# BalEv_FPTG_IO_v1_0.net
KiCad netlist of a schematic drawn in Altium Designer
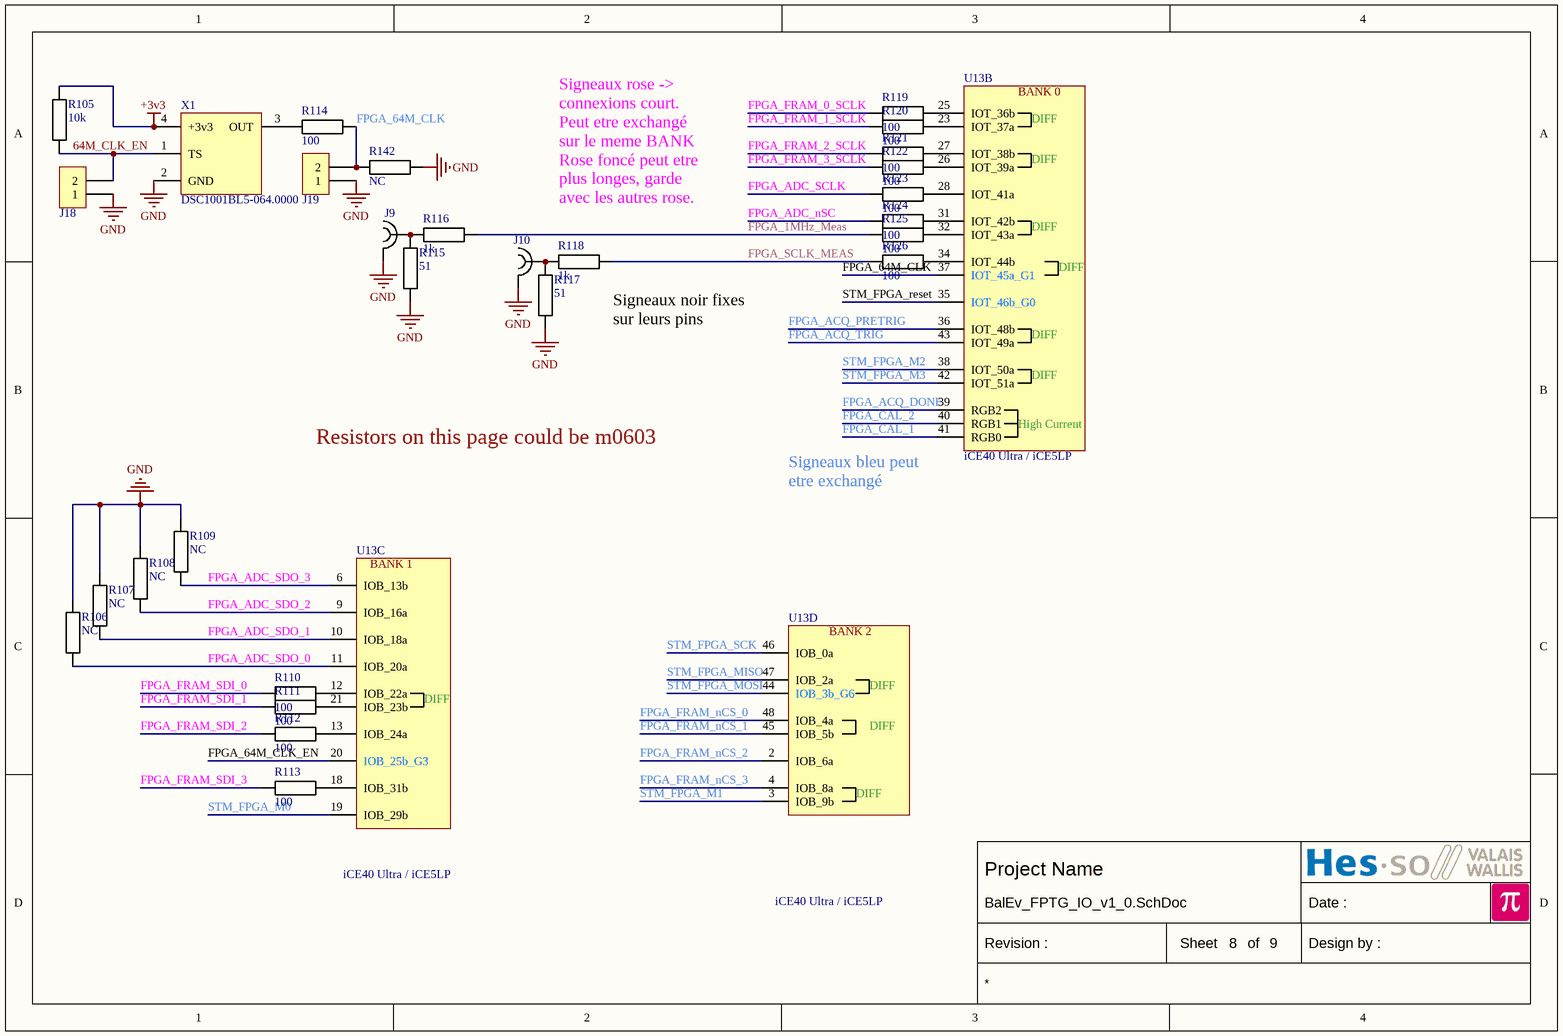
[diagram p0: BalEv_FPTG_IO_v1_0.SchDoc]

(export (version "E")
  (design (tool "Eeschema 10.0.6"))
  (components
    (comp (ref "J9")
      (value "CONSMA001-SMD-G")
      (footprint "SMA SMD Vertical Linx CONSMA001-SMD-G")
      (description "SMA TH VERTICAL LINX CONSMA001-SMD-G")
      (libsource (lib "Connector") (part "SMA SMD VERTICAL LINX CONSMA001-SMD-G"))
    )
    (comp (ref "J10")
      (value "CONSMA001-SMD-G")
      (footprint "SMA SMD Vertical Linx CONSMA001-SMD-G")
      (description "SMA TH VERTICAL LINX CONSMA001-SMD-G")
      (libsource (lib "Connector") (part "SMA SMD VERTICAL LINX CONSMA001-SMD-G"))
    )
    (comp (ref "J18")
      (value "*")
      (footprint "PinHeader1x2 P2.54")
      (description "Plug connector")
      (libsource (lib "PinHeader") (part "PinHeader1x2"))
    )
    (comp (ref "J19")
      (value "*")
      (footprint "PinHeader1x2 P1.27")
      (description "Plug connector")
      (libsource (lib "PinHeader") (part "PinHeader1x2"))
    )
    (comp (ref "R105")
      (value "10k")
      (footprint "RESISTOR 1005 REFLOW")
      (description "Resistor")
      (libsource (lib "Resistor") (part "Resistor"))
    )
    (comp (ref "R106")
      (value "NC")
      (footprint "RESISTOR 1005 REFLOW")
      (description "Resistor")
      (libsource (lib "Resistor") (part "Resistor"))
    )
    (comp (ref "R107")
      (value "NC")
      (footprint "RESISTOR 1005 REFLOW")
      (description "Resistor")
      (libsource (lib "Resistor") (part "Resistor"))
    )
    (comp (ref "R108")
      (value "NC")
      (footprint "RESISTOR 1005 REFLOW")
      (description "Resistor")
      (libsource (lib "Resistor") (part "Resistor"))
    )
    (comp (ref "R109")
      (value "NC")
      (footprint "RESISTOR 1005 REFLOW")
      (description "Resistor")
      (libsource (lib "Resistor") (part "Resistor"))
    )
    (comp (ref "R110")
      (value "100")
      (footprint "RESISTOR 1005 REFLOW")
      (description "Resistor")
      (libsource (lib "Resistor") (part "Resistor"))
    )
    (comp (ref "R111")
      (value "100")
      (footprint "RESISTOR 1005 REFLOW")
      (description "Resistor")
      (libsource (lib "Resistor") (part "Resistor"))
    )
    (comp (ref "R112")
      (value "100")
      (footprint "RESISTOR 1005 REFLOW")
      (description "Resistor")
      (libsource (lib "Resistor") (part "Resistor"))
    )
    (comp (ref "R113")
      (value "100")
      (footprint "RESISTOR 1005 REFLOW")
      (description "Resistor")
      (libsource (lib "Resistor") (part "Resistor"))
    )
    (comp (ref "R114")
      (value "100")
      (footprint "RESISTOR 1005 REFLOW")
      (description "Resistor")
      (libsource (lib "Resistor") (part "Resistor"))
    )
    (comp (ref "R115")
      (value "51")
      (footprint "RESISTOR 1005 REFLOW")
      (description "Resistor")
      (libsource (lib "Resistor") (part "Resistor"))
    )
    (comp (ref "R116")
      (value "1k")
      (footprint "RESISTOR 1005 REFLOW")
      (description "Resistor")
      (libsource (lib "Resistor") (part "Resistor"))
    )
    (comp (ref "R117")
      (value "51")
      (footprint "RESISTOR 1005 REFLOW")
      (description "Resistor")
      (libsource (lib "Resistor") (part "Resistor"))
    )
    (comp (ref "R118")
      (value "1k")
      (footprint "RESISTOR 1005 REFLOW")
      (description "Resistor")
      (libsource (lib "Resistor") (part "Resistor"))
    )
    (comp (ref "R119")
      (value "100")
      (footprint "RESISTOR 1005 REFLOW")
      (description "Resistor")
      (libsource (lib "Resistor") (part "Resistor"))
    )
    (comp (ref "R120")
      (value "100")
      (footprint "RESISTOR 1005 REFLOW")
      (description "Resistor")
      (libsource (lib "Resistor") (part "Resistor"))
    )
    (comp (ref "R121")
      (value "100")
      (footprint "RESISTOR 1005 REFLOW")
      (description "Resistor")
      (libsource (lib "Resistor") (part "Resistor"))
    )
    (comp (ref "R122")
      (value "100")
      (footprint "RESISTOR 1005 REFLOW")
      (description "Resistor")
      (libsource (lib "Resistor") (part "Resistor"))
    )
    (comp (ref "R123")
      (value "100")
      (footprint "RESISTOR 1005 REFLOW")
      (description "Resistor")
      (libsource (lib "Resistor") (part "Resistor"))
    )
    (comp (ref "R124")
      (value "100")
      (footprint "RESISTOR 1005 REFLOW")
      (description "Resistor")
      (libsource (lib "Resistor") (part "Resistor"))
    )
    (comp (ref "R125")
      (value "100")
      (footprint "RESISTOR 1005 REFLOW")
      (description "Resistor")
      (libsource (lib "Resistor") (part "Resistor"))
    )
    (comp (ref "R126")
      (value "100")
      (footprint "RESISTOR 1005 REFLOW")
      (description "Resistor")
      (libsource (lib "Resistor") (part "Resistor"))
    )
    (comp (ref "R142")
      (value "NC")
      (footprint "RESISTOR 1005 REFLOW")
      (description "Resistor")
      (libsource (lib "Resistor") (part "Resistor"))
    )
    (comp (ref "U13")
      (value "iCE40 Ultra / iCE5LP")
      (footprint "QFN50P700X700X100_HS-49N")
      (libsource (lib "IntegratedCircuit") (part "ICE5LP1K-SG48"))
    )
    (comp (ref "X1")
      (value "DSC1001BL5-064.0000")
      (footprint "Oscillator C5.0x3.2 Abracon ASFL1")
      (description "Oscillator C5.0x3.2 Abracon ASFL1")
      (libsource (lib "Oscillator") (part "Oscillator C5.0x3.2 Abracon ASFL1"))
    )
  )
  (nets
    (net (code "1") (name "+3v3") (class "Default")
      (node (ref "R105") (pin "2") (pinfunction "2_2") (pintype "passive"))
      (node (ref "X1") (pin "4") (pinfunction "+3v3_4") (pintype "passive"))
    )
    (net (code "2") (name "/64M_CLK_EN") (class "Default")
      (node (ref "J18") (pin "2") (pinfunction "2_2") (pintype "passive"))
      (node (ref "R105") (pin "1") (pinfunction "1_1") (pintype "passive"))
      (node (ref "X1") (pin "1") (pinfunction "TS_1") (pintype "passive"))
    )
    (net (code "3") (name "/FPGA_1MHz_Meas") (class "Default")
      (node (ref "R116") (pin "1") (pinfunction "1_1") (pintype "passive"))
      (node (ref "R125") (pin "2") (pinfunction "2_2") (pintype "passive"))
    )
    (net (code "4") (name "/FPGA_64M_CLK") (class "Default")
      (node (ref "J19") (pin "2") (pinfunction "2_2") (pintype "passive"))
      (node (ref "R114") (pin "1") (pinfunction "1_1") (pintype "passive"))
      (node (ref "R142") (pin "2") (pinfunction "2_2") (pintype "passive"))
      (node (ref "U13") (pin "37") (pinfunction "IOT_45a_G1_37") (pintype "passive"))
    )
    (net (code "5") (name "/FPGA_64M_CLK_EN") (class "Default")
      (node (ref "U13") (pin "20") (pinfunction "IOB_25b_G3_20") (pintype "passive"))
    )
    (net (code "6") (name "/FPGA_ACQ_DONE") (class "Default")
      (node (ref "U13") (pin "39") (pinfunction "RGB2_39") (pintype "passive"))
    )
    (net (code "7") (name "/FPGA_ACQ_PRETRIG") (class "Default")
      (node (ref "U13") (pin "36") (pinfunction "IOT_48b_36") (pintype "passive"))
    )
    (net (code "8") (name "/FPGA_ACQ_TRIG") (class "Default")
      (node (ref "U13") (pin "43") (pinfunction "IOT_49a_43") (pintype "passive"))
    )
    (net (code "9") (name "/FPGA_ADC_SCLK") (class "Default")
      (node (ref "R123") (pin "2") (pinfunction "2_2") (pintype "passive"))
    )
    (net (code "10") (name "/FPGA_ADC_SDO_0") (class "Default")
      (node (ref "R106") (pin "2") (pinfunction "2_2") (pintype "passive"))
      (node (ref "U13") (pin "11") (pinfunction "IOB_20a_11") (pintype "passive"))
    )
    (net (code "11") (name "/FPGA_ADC_SDO_1") (class "Default")
      (node (ref "R107") (pin "2") (pinfunction "2_2") (pintype "passive"))
      (node (ref "U13") (pin "10") (pinfunction "IOB_18a_10") (pintype "passive"))
    )
    (net (code "12") (name "/FPGA_ADC_SDO_2") (class "Default")
      (node (ref "R108") (pin "2") (pinfunction "2_2") (pintype "passive"))
      (node (ref "U13") (pin "9") (pinfunction "IOB_16a_9") (pintype "passive"))
    )
    (net (code "13") (name "/FPGA_ADC_SDO_3") (class "Default")
      (node (ref "R109") (pin "2") (pinfunction "2_2") (pintype "passive"))
      (node (ref "U13") (pin "6") (pinfunction "IOB_13b_6") (pintype "passive"))
    )
    (net (code "14") (name "/FPGA_ADC_nSC") (class "Default")
      (node (ref "R124") (pin "2") (pinfunction "2_2") (pintype "passive"))
    )
    (net (code "15") (name "/FPGA_CAL_1") (class "Default")
      (node (ref "U13") (pin "41") (pinfunction "RGB0_41") (pintype "passive"))
    )
    (net (code "16") (name "/FPGA_CAL_2") (class "Default")
      (node (ref "U13") (pin "40") (pinfunction "RGB1_40") (pintype "passive"))
    )
    (net (code "17") (name "/FPGA_FRAM_0_SCLK") (class "Default")
      (node (ref "R119") (pin "2") (pinfunction "2_2") (pintype "passive"))
    )
    (net (code "18") (name "/FPGA_FRAM_1_SCLK") (class "Default")
      (node (ref "R120") (pin "2") (pinfunction "2_2") (pintype "passive"))
    )
    (net (code "19") (name "/FPGA_FRAM_2_SCLK") (class "Default")
      (node (ref "R121") (pin "2") (pinfunction "2_2") (pintype "passive"))
    )
    (net (code "20") (name "/FPGA_FRAM_3_SCLK") (class "Default")
      (node (ref "R122") (pin "2") (pinfunction "2_2") (pintype "passive"))
    )
    (net (code "21") (name "/FPGA_FRAM_SDI_0") (class "Default")
      (node (ref "R110") (pin "2") (pinfunction "2_2") (pintype "passive"))
    )
    (net (code "22") (name "/FPGA_FRAM_SDI_1") (class "Default")
      (node (ref "R111") (pin "2") (pinfunction "2_2") (pintype "passive"))
    )
    (net (code "23") (name "/FPGA_FRAM_SDI_2") (class "Default")
      (node (ref "R112") (pin "2") (pinfunction "2_2") (pintype "passive"))
    )
    (net (code "24") (name "/FPGA_FRAM_SDI_3") (class "Default")
      (node (ref "R113") (pin "2") (pinfunction "2_2") (pintype "passive"))
    )
    (net (code "25") (name "/FPGA_FRAM_nCS_0") (class "Default")
      (node (ref "U13") (pin "48") (pinfunction "IOB_4a_48") (pintype "passive"))
    )
    (net (code "26") (name "/FPGA_FRAM_nCS_1") (class "Default")
      (node (ref "U13") (pin "45") (pinfunction "IOB_5b_45") (pintype "passive"))
    )
    (net (code "27") (name "/FPGA_FRAM_nCS_2") (class "Default")
      (node (ref "U13") (pin "2") (pinfunction "IOB_6a_2") (pintype "passive"))
    )
    (net (code "28") (name "/FPGA_FRAM_nCS_3") (class "Default")
      (node (ref "U13") (pin "4") (pinfunction "IOB_8a_4") (pintype "passive"))
    )
    (net (code "29") (name "/FPGA_SCLK_MEAS") (class "Default")
      (node (ref "R118") (pin "1") (pinfunction "1_1") (pintype "passive"))
      (node (ref "R126") (pin "2") (pinfunction "2_2") (pintype "passive"))
    )
    (net (code "30") (name "/STM_FPGA_M0") (class "Default")
      (node (ref "U13") (pin "19") (pinfunction "IOB_29b_19") (pintype "passive"))
    )
    (net (code "31") (name "/STM_FPGA_M1") (class "Default")
      (node (ref "U13") (pin "3") (pinfunction "IOB_9b_3") (pintype "passive"))
    )
    (net (code "32") (name "/STM_FPGA_M2") (class "Default")
      (node (ref "U13") (pin "38") (pinfunction "IOT_50a_38") (pintype "passive"))
    )
    (net (code "33") (name "/STM_FPGA_M3") (class "Default")
      (node (ref "U13") (pin "42") (pinfunction "IOT_51a_42") (pintype "passive"))
    )
    (net (code "34") (name "/STM_FPGA_MISO") (class "Default")
      (node (ref "U13") (pin "47") (pinfunction "IOB_2a_47") (pintype "passive"))
    )
    (net (code "35") (name "/STM_FPGA_MOSI") (class "Default")
      (node (ref "U13") (pin "44") (pinfunction "IOB_3b_G6_44") (pintype "passive"))
    )
    (net (code "36") (name "/STM_FPGA_SCK") (class "Default")
      (node (ref "U13") (pin "46") (pinfunction "IOB_0a_46") (pintype "passive"))
    )
    (net (code "37") (name "/STM_FPGA_reset") (class "Default")
      (node (ref "U13") (pin "35") (pinfunction "IOT_46b_G0_35") (pintype "passive"))
    )
    (net (code "38") (name "GND") (class "Default")
      (node (ref "J10") (pin "2") (pinfunction "2_2") (pintype "passive"))
      (node (ref "J18") (pin "1") (pinfunction "1_1") (pintype "passive"))
      (node (ref "J19") (pin "1") (pinfunction "1_1") (pintype "passive"))
      (node (ref "J9") (pin "2") (pinfunction "2_2") (pintype "passive"))
      (node (ref "R106") (pin "1") (pinfunction "1_1") (pintype "passive"))
      (node (ref "R107") (pin "1") (pinfunction "1_1") (pintype "passive"))
      (node (ref "R108") (pin "1") (pinfunction "1_1") (pintype "passive"))
      (node (ref "R109") (pin "1") (pinfunction "1_1") (pintype "passive"))
      (node (ref "R115") (pin "2") (pinfunction "2_2") (pintype "passive"))
      (node (ref "R117") (pin "2") (pinfunction "2_2") (pintype "passive"))
      (node (ref "R142") (pin "1") (pinfunction "1_1") (pintype "passive"))
      (node (ref "X1") (pin "2") (pinfunction "GND_2") (pintype "passive"))
    )
    (net (code "39") (name "Net-(J9-Pad1)") (class "Default")
      (node (ref "J9") (pin "1") (pinfunction "1_1") (pintype "passive"))
      (node (ref "R115") (pin "1") (pinfunction "1_1") (pintype "passive"))
      (node (ref "R116") (pin "2") (pinfunction "2_2") (pintype "passive"))
    )
    (net (code "40") (name "Net-(J10-Pad1)") (class "Default")
      (node (ref "J10") (pin "1") (pinfunction "1_1") (pintype "passive"))
      (node (ref "R117") (pin "1") (pinfunction "1_1") (pintype "passive"))
      (node (ref "R118") (pin "2") (pinfunction "2_2") (pintype "passive"))
    )
    (net (code "41") (name "Net-(U13B-IOT_36b)") (class "Default")
      (node (ref "R119") (pin "1") (pinfunction "1_1") (pintype "passive"))
      (node (ref "U13") (pin "25") (pinfunction "IOT_36b_25") (pintype "passive"))
    )
    (net (code "42") (name "Net-(U13B-IOT_37a)") (class "Default")
      (node (ref "R120") (pin "1") (pinfunction "1_1") (pintype "passive"))
      (node (ref "U13") (pin "23") (pinfunction "IOT_37a_23") (pintype "passive"))
    )
    (net (code "43") (name "Net-(U13B-IOT_38b)") (class "Default")
      (node (ref "R121") (pin "1") (pinfunction "1_1") (pintype "passive"))
      (node (ref "U13") (pin "27") (pinfunction "IOT_38b_27") (pintype "passive"))
    )
    (net (code "44") (name "Net-(U13B-IOT_39a)") (class "Default")
      (node (ref "R122") (pin "1") (pinfunction "1_1") (pintype "passive"))
      (node (ref "U13") (pin "26") (pinfunction "IOT_39a_26") (pintype "passive"))
    )
    (net (code "45") (name "Net-(U13B-IOT_41a)") (class "Default")
      (node (ref "R123") (pin "1") (pinfunction "1_1") (pintype "passive"))
      (node (ref "U13") (pin "28") (pinfunction "IOT_41a_28") (pintype "passive"))
    )
    (net (code "46") (name "Net-(U13B-IOT_42b)") (class "Default")
      (node (ref "R124") (pin "1") (pinfunction "1_1") (pintype "passive"))
      (node (ref "U13") (pin "31") (pinfunction "IOT_42b_31") (pintype "passive"))
    )
    (net (code "47") (name "Net-(U13B-IOT_43a)") (class "Default")
      (node (ref "R125") (pin "1") (pinfunction "1_1") (pintype "passive"))
      (node (ref "U13") (pin "32") (pinfunction "IOT_43a_32") (pintype "passive"))
    )
    (net (code "48") (name "Net-(U13B-IOT_44b)") (class "Default")
      (node (ref "R126") (pin "1") (pinfunction "1_1") (pintype "passive"))
      (node (ref "U13") (pin "34") (pinfunction "IOT_44b_34") (pintype "passive"))
    )
    (net (code "49") (name "Net-(U13C-IOB_22a)") (class "Default")
      (node (ref "R110") (pin "1") (pinfunction "1_1") (pintype "passive"))
      (node (ref "U13") (pin "12") (pinfunction "IOB_22a_12") (pintype "passive"))
    )
    (net (code "50") (name "Net-(U13C-IOB_23b)") (class "Default")
      (node (ref "R111") (pin "1") (pinfunction "1_1") (pintype "passive"))
      (node (ref "U13") (pin "21") (pinfunction "IOB_23b_21") (pintype "passive"))
    )
    (net (code "51") (name "Net-(U13C-IOB_24a)") (class "Default")
      (node (ref "R112") (pin "1") (pinfunction "1_1") (pintype "passive"))
      (node (ref "U13") (pin "13") (pinfunction "IOB_24a_13") (pintype "passive"))
    )
    (net (code "52") (name "Net-(U13C-IOB_31b)") (class "Default")
      (node (ref "R113") (pin "1") (pinfunction "1_1") (pintype "passive"))
      (node (ref "U13") (pin "18") (pinfunction "IOB_31b_18") (pintype "passive"))
    )
    (net (code "53") (name "Net-(X1-OUT)") (class "Default")
      (node (ref "R114") (pin "2") (pinfunction "2_2") (pintype "passive"))
      (node (ref "X1") (pin "3") (pinfunction "OUT_3") (pintype "passive"))
    )
  )
)
